# 20_MCU_BLE.net
KiCad netlist of a schematic drawn in Altium Designer
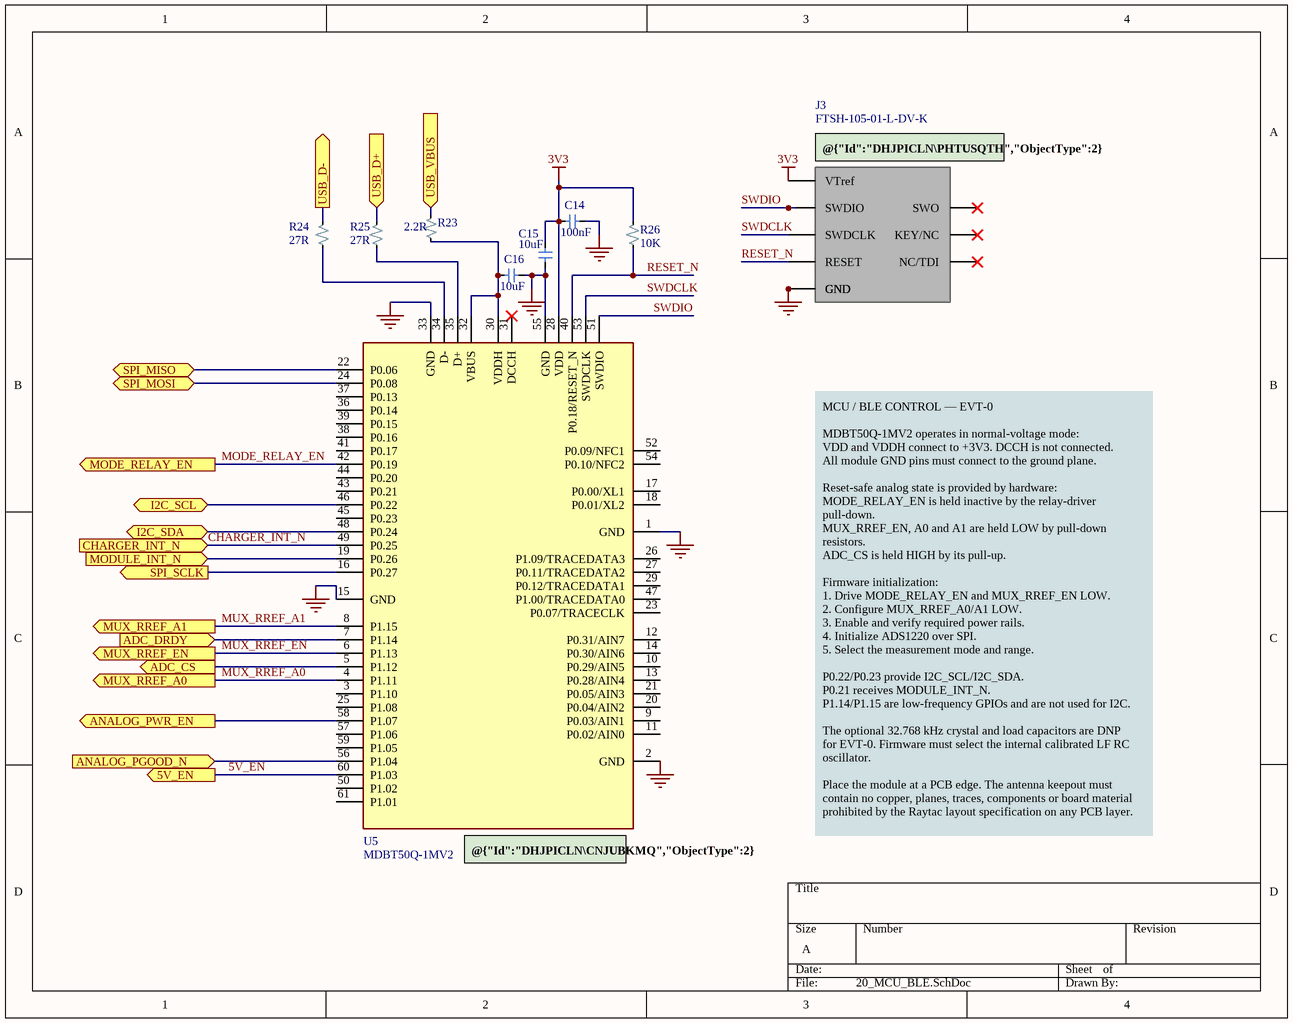
[diagram p0: 20_MCU_BLE.SchDoc]

(export (version "E")
  (design (tool "Eeschema 10.0.6"))
  (components
    (comp (ref "C14")
      (value "100nF")
      (footprint "C0805")
      (libsource (lib "PocketLab_DMM_SchLib") (part "C_0805"))
    )
    (comp (ref "C15")
      (value "10uF")
      (footprint "C0805")
      (libsource (lib "PocketLab_DMM_SchLib") (part "C_0805"))
    )
    (comp (ref "C16")
      (value "10uF")
      (footprint "C0805")
      (libsource (lib "PocketLab_DMM_SchLib") (part "C_0805"))
    )
    (comp (ref "J3")
      (value "FTSH-105-01-L-DV-K")
      (footprint "FTSH-105-01-L-DV-K")
      (description "CONN HEADER SMD 10POS 1.27MM / Connector Header Surface Mount 10 position 0.050\" (1.27mm)")
      (fields (field (name "MANUFACTURER") "Samtec"))
      (libsource (lib "PocketLab_DMM_SchLib") (part "FTSH-105-01-L-DV-K"))
    )
    (comp (ref "R23")
      (value "2.2R")
      (footprint "R0805")
      (description "RES 1/8W 0805")
      (fields
        (field (name "MANUFACTURER") "Stackpole Electronics")
        (field (name "MANUFACTURER PART NUMBER") "RNCF0805TKY10K0")
      )
      (libsource (lib "PocketLab_DMM_SchLib") (part "R_0805"))
    )
    (comp (ref "R24")
      (value "27R")
      (footprint "R0805")
      (description "RES 1/8W 0805")
      (fields
        (field (name "MANUFACTURER") "Stackpole Electronics")
        (field (name "MANUFACTURER PART NUMBER") "RNCF0805TKY10K0")
      )
      (libsource (lib "PocketLab_DMM_SchLib") (part "R_0805"))
    )
    (comp (ref "R25")
      (value "27R")
      (footprint "R0805")
      (description "RES 1/8W 0805")
      (fields
        (field (name "MANUFACTURER") "Stackpole Electronics")
        (field (name "MANUFACTURER PART NUMBER") "RNCF0805TKY10K0")
      )
      (libsource (lib "PocketLab_DMM_SchLib") (part "R_0805"))
    )
    (comp (ref "R26")
      (value "10K")
      (footprint "R0805")
      (description "RES 1/8W 0805")
      (fields
        (field (name "MANUFACTURER") "Stackpole Electronics")
        (field (name "MANUFACTURER PART NUMBER") "RNCF0805TKY10K0")
      )
      (libsource (lib "PocketLab_DMM_SchLib") (part "R_0805"))
    )
    (comp (ref "U5")
      (value "MDBT50Q-1MV2")
      (footprint "NRF52840_MDBT50Q-1MV2")
      (fields (field (name "MF") "Raytac Corporation"))
      (libsource (lib "PocketLab_DMM_EVT0") (part "MDBT50Q-1MV2"))
    )
  )
  (nets
    (net (code "1") (name "/5V_EN") (class "Default")
      (node (ref "U5") (pin "60") (pinfunction "P1.03_60") (pintype "passive"))
    )
    (net (code "2") (name "/ADC_CS") (class "Default")
      (node (ref "U5") (pin "5") (pinfunction "P1.12_5") (pintype "passive"))
    )
    (net (code "3") (name "/ADC_DRDY") (class "Default")
      (node (ref "U5") (pin "7") (pinfunction "P1.14_7") (pintype "passive"))
    )
    (net (code "4") (name "/ANALOG_PGOOD_N") (class "Default")
      (node (ref "U5") (pin "56") (pinfunction "P1.04_56") (pintype "passive"))
    )
    (net (code "5") (name "/ANALOG_PWR_EN") (class "Default")
      (node (ref "U5") (pin "58") (pinfunction "P1.07_58") (pintype "passive"))
    )
    (net (code "6") (name "/CHARGER_INT_N") (class "Default")
      (node (ref "U5") (pin "49") (pinfunction "P0.25_49") (pintype "passive"))
    )
    (net (code "7") (name "/I2C_SCL") (class "Default")
      (node (ref "U5") (pin "46") (pinfunction "P0.22_46") (pintype "passive"))
    )
    (net (code "8") (name "/I2C_SDA") (class "Default")
      (node (ref "U5") (pin "48") (pinfunction "P0.24_48") (pintype "passive"))
    )
    (net (code "9") (name "/MODE_RELAY_EN") (class "Default")
      (node (ref "U5") (pin "42") (pinfunction "P0.19_42") (pintype "passive"))
    )
    (net (code "10") (name "/MODULE_INT_N") (class "Default")
      (node (ref "U5") (pin "19") (pinfunction "P0.26_19") (pintype "passive"))
    )
    (net (code "11") (name "/MUX_RREF_A0") (class "Default")
      (node (ref "U5") (pin "4") (pinfunction "P1.11_4") (pintype "passive"))
    )
    (net (code "12") (name "/MUX_RREF_A1") (class "Default")
      (node (ref "U5") (pin "8") (pinfunction "P1.15_8") (pintype "passive"))
    )
    (net (code "13") (name "/MUX_RREF_EN") (class "Default")
      (node (ref "U5") (pin "6") (pinfunction "P1.13_6") (pintype "passive"))
    )
    (net (code "14") (name "/RESET_N") (class "Default")
      (node (ref "J3") (pin "10") (pinfunction "RESET_10") (pintype "passive"))
      (node (ref "R26") (pin "1") (pinfunction "1_1") (pintype "passive"))
      (node (ref "U5") (pin "40") (pinfunction "P0.18/RESET_N_40") (pintype "passive"))
    )
    (net (code "15") (name "/SPI_MISO") (class "Default")
      (node (ref "U5") (pin "22") (pinfunction "P0.06_22") (pintype "passive"))
    )
    (net (code "16") (name "/SPI_MOSI") (class "Default")
      (node (ref "U5") (pin "24") (pinfunction "P0.08_24") (pintype "passive"))
    )
    (net (code "17") (name "/SPI_SCLK") (class "Default")
      (node (ref "U5") (pin "16") (pinfunction "P0.27_16") (pintype "passive"))
    )
    (net (code "18") (name "/SWDCLK") (class "Default")
      (node (ref "J3") (pin "4") (pinfunction "SWDCLK_4") (pintype "passive"))
      (node (ref "U5") (pin "53") (pinfunction "SWDCLK_53") (pintype "passive"))
    )
    (net (code "19") (name "/SWDIO") (class "Default")
      (node (ref "J3") (pin "2") (pinfunction "SWDIO_2") (pintype "passive"))
      (node (ref "U5") (pin "51") (pinfunction "SWDIO_51") (pintype "passive"))
    )
    (net (code "20") (name "/USB_D+") (class "Default")
      (node (ref "R25") (pin "2") (pinfunction "2_2") (pintype "passive"))
    )
    (net (code "21") (name "/USB_D-") (class "Default")
      (node (ref "R24") (pin "2") (pinfunction "2_2") (pintype "passive"))
    )
    (net (code "22") (name "/USB_VBUS") (class "Default")
      (node (ref "R23") (pin "2") (pinfunction "2_2") (pintype "passive"))
    )
    (net (code "23") (name "3V3") (class "Default")
      (node (ref "C14") (pin "1") (pinfunction "1_1") (pintype "passive"))
      (node (ref "C15") (pin "1") (pinfunction "1_1") (pintype "passive"))
      (node (ref "J3") (pin "1") (pinfunction "VTref_1") (pintype "passive"))
      (node (ref "R26") (pin "2") (pinfunction "2_2") (pintype "passive"))
      (node (ref "U5") (pin "28") (pinfunction "VDD_28") (pintype "passive"))
    )
    (net (code "24") (name "GND") (class "Default")
      (node (ref "C14") (pin "2") (pinfunction "2_2") (pintype "passive"))
      (node (ref "C15") (pin "2") (pinfunction "2_2") (pintype "passive"))
      (node (ref "C16") (pin "2") (pinfunction "2_2") (pintype "passive"))
      (node (ref "J3") (pin "3") (pinfunction "GND_3") (pintype "passive"))
      (node (ref "J3") (pin "5") (pinfunction "GND_5") (pintype "passive"))
      (node (ref "J3") (pin "9") (pinfunction "GND_9") (pintype "passive"))
      (node (ref "U5") (pin "1") (pinfunction "GND_1") (pintype "passive"))
      (node (ref "U5") (pin "15") (pinfunction "GND_15") (pintype "passive"))
      (node (ref "U5") (pin "2") (pinfunction "GND_2") (pintype "passive"))
      (node (ref "U5") (pin "33") (pinfunction "GND_33") (pintype "passive"))
      (node (ref "U5") (pin "55") (pinfunction "GND_55") (pintype "passive"))
    )
    (net (code "25") (name "Net-(U5-D+)") (class "Default")
      (node (ref "R25") (pin "1") (pinfunction "1_1") (pintype "passive"))
      (node (ref "U5") (pin "35") (pinfunction "D+_35") (pintype "passive"))
    )
    (net (code "26") (name "Net-(U5-D-)") (class "Default")
      (node (ref "R24") (pin "1") (pinfunction "1_1") (pintype "passive"))
      (node (ref "U5") (pin "34") (pinfunction "D-_34") (pintype "passive"))
    )
    (net (code "27") (name "Net-(U5-VBUS)") (class "Default")
      (node (ref "C16") (pin "1") (pinfunction "1_1") (pintype "passive"))
      (node (ref "R23") (pin "1") (pinfunction "1_1") (pintype "passive"))
      (node (ref "U5") (pin "30") (pinfunction "VDDH_30") (pintype "passive"))
      (node (ref "U5") (pin "32") (pinfunction "VBUS_32") (pintype "passive"))
    )
    (net (code "28") (name "unconnected-(J3-KEY{slash}NC-Pad7)") (class "Default")
      (node (ref "J3") (pin "7") (pinfunction "KEY/NC_7") (pintype "passive+no_connect"))
    )
    (net (code "29") (name "unconnected-(J3-NC{slash}TDI-Pad8)") (class "Default")
      (node (ref "J3") (pin "8") (pinfunction "NC/TDI_8") (pintype "passive+no_connect"))
    )
    (net (code "30") (name "unconnected-(J3-SWO-Pad6)") (class "Default")
      (node (ref "J3") (pin "6") (pinfunction "SWO_6") (pintype "passive+no_connect"))
    )
    (net (code "31") (name "unconnected-(U5-DCCH-Pad31)") (class "Default")
      (node (ref "U5") (pin "31") (pinfunction "DCCH_31") (pintype "passive+no_connect"))
    )
    (net (code "32") (name "unconnected-(U5-P0.00{slash}XL1-Pad17)") (class "Default")
      (node (ref "U5") (pin "17") (pinfunction "P0.00/XL1_17") (pintype "passive"))
    )
    (net (code "33") (name "unconnected-(U5-P0.01{slash}XL2-Pad18)") (class "Default")
      (node (ref "U5") (pin "18") (pinfunction "P0.01/XL2_18") (pintype "passive"))
    )
    (net (code "34") (name "unconnected-(U5-P0.02{slash}AIN0-Pad11)") (class "Default")
      (node (ref "U5") (pin "11") (pinfunction "P0.02/AIN0_11") (pintype "passive"))
    )
    (net (code "35") (name "unconnected-(U5-P0.03{slash}AIN1-Pad9)") (class "Default")
      (node (ref "U5") (pin "9") (pinfunction "P0.03/AIN1_9") (pintype "passive"))
    )
    (net (code "36") (name "unconnected-(U5-P0.04{slash}AIN2-Pad20)") (class "Default")
      (node (ref "U5") (pin "20") (pinfunction "P0.04/AIN2_20") (pintype "passive"))
    )
    (net (code "37") (name "unconnected-(U5-P0.05{slash}AIN3-Pad21)") (class "Default")
      (node (ref "U5") (pin "21") (pinfunction "P0.05/AIN3_21") (pintype "passive"))
    )
    (net (code "38") (name "unconnected-(U5-P0.07{slash}TRACECLK-Pad23)") (class "Default")
      (node (ref "U5") (pin "23") (pinfunction "P0.07/TRACECLK_23") (pintype "passive"))
    )
    (net (code "39") (name "unconnected-(U5-P0.09{slash}NFC1-Pad52)") (class "Default")
      (node (ref "U5") (pin "52") (pinfunction "P0.09/NFC1_52") (pintype "passive"))
    )
    (net (code "40") (name "unconnected-(U5-P0.10{slash}NFC2-Pad54)") (class "Default")
      (node (ref "U5") (pin "54") (pinfunction "P0.10/NFC2_54") (pintype "passive"))
    )
    (net (code "41") (name "unconnected-(U5-P0.11{slash}TRACEDATA2-Pad27)") (class "Default")
      (node (ref "U5") (pin "27") (pinfunction "P0.11/TRACEDATA2_27") (pintype "passive"))
    )
    (net (code "42") (name "unconnected-(U5-P0.12{slash}TRACEDATA1-Pad29)") (class "Default")
      (node (ref "U5") (pin "29") (pinfunction "P0.12/TRACEDATA1_29") (pintype "passive"))
    )
    (net (code "43") (name "unconnected-(U5-P0.13-Pad37)") (class "Default")
      (node (ref "U5") (pin "37") (pinfunction "P0.13_37") (pintype "passive"))
    )
    (net (code "44") (name "unconnected-(U5-P0.14-Pad36)") (class "Default")
      (node (ref "U5") (pin "36") (pinfunction "P0.14_36") (pintype "passive"))
    )
    (net (code "45") (name "unconnected-(U5-P0.15-Pad39)") (class "Default")
      (node (ref "U5") (pin "39") (pinfunction "P0.15_39") (pintype "passive"))
    )
    (net (code "46") (name "unconnected-(U5-P0.16-Pad38)") (class "Default")
      (node (ref "U5") (pin "38") (pinfunction "P0.16_38") (pintype "passive"))
    )
    (net (code "47") (name "unconnected-(U5-P0.17-Pad41)") (class "Default")
      (node (ref "U5") (pin "41") (pinfunction "P0.17_41") (pintype "passive"))
    )
    (net (code "48") (name "unconnected-(U5-P0.20-Pad44)") (class "Default")
      (node (ref "U5") (pin "44") (pinfunction "P0.20_44") (pintype "passive"))
    )
    (net (code "49") (name "unconnected-(U5-P0.21-Pad43)") (class "Default")
      (node (ref "U5") (pin "43") (pinfunction "P0.21_43") (pintype "passive"))
    )
    (net (code "50") (name "unconnected-(U5-P0.23-Pad45)") (class "Default")
      (node (ref "U5") (pin "45") (pinfunction "P0.23_45") (pintype "passive"))
    )
    (net (code "51") (name "unconnected-(U5-P0.28{slash}AIN4-Pad13)") (class "Default")
      (node (ref "U5") (pin "13") (pinfunction "P0.28/AIN4_13") (pintype "passive"))
    )
    (net (code "52") (name "unconnected-(U5-P0.29{slash}AIN5-Pad10)") (class "Default")
      (node (ref "U5") (pin "10") (pinfunction "P0.29/AIN5_10") (pintype "passive"))
    )
    (net (code "53") (name "unconnected-(U5-P0.30{slash}AIN6-Pad14)") (class "Default")
      (node (ref "U5") (pin "14") (pinfunction "P0.30/AIN6_14") (pintype "passive"))
    )
    (net (code "54") (name "unconnected-(U5-P0.31{slash}AIN7-Pad12)") (class "Default")
      (node (ref "U5") (pin "12") (pinfunction "P0.31/AIN7_12") (pintype "passive"))
    )
    (net (code "55") (name "unconnected-(U5-P1.00{slash}TRACEDATA0-Pad47)") (class "Default")
      (node (ref "U5") (pin "47") (pinfunction "P1.00/TRACEDATA0_47") (pintype "passive"))
    )
    (net (code "56") (name "unconnected-(U5-P1.01-Pad61)") (class "Default")
      (node (ref "U5") (pin "61") (pinfunction "P1.01_61") (pintype "passive"))
    )
    (net (code "57") (name "unconnected-(U5-P1.02-Pad50)") (class "Default")
      (node (ref "U5") (pin "50") (pinfunction "P1.02_50") (pintype "passive"))
    )
    (net (code "58") (name "unconnected-(U5-P1.05-Pad59)") (class "Default")
      (node (ref "U5") (pin "59") (pinfunction "P1.05_59") (pintype "passive"))
    )
    (net (code "59") (name "unconnected-(U5-P1.06-Pad57)") (class "Default")
      (node (ref "U5") (pin "57") (pinfunction "P1.06_57") (pintype "passive"))
    )
    (net (code "60") (name "unconnected-(U5-P1.08-Pad25)") (class "Default")
      (node (ref "U5") (pin "25") (pinfunction "P1.08_25") (pintype "passive"))
    )
    (net (code "61") (name "unconnected-(U5-P1.09{slash}TRACEDATA3-Pad26)") (class "Default")
      (node (ref "U5") (pin "26") (pinfunction "P1.09/TRACEDATA3_26") (pintype "passive"))
    )
    (net (code "62") (name "unconnected-(U5-P1.10-Pad3)") (class "Default")
      (node (ref "U5") (pin "3") (pinfunction "P1.10_3") (pintype "passive"))
    )
  )
)
